# McPiFace-Pi4-V1_0.net
KiCad netlist of a schematic drawn in EAGLE
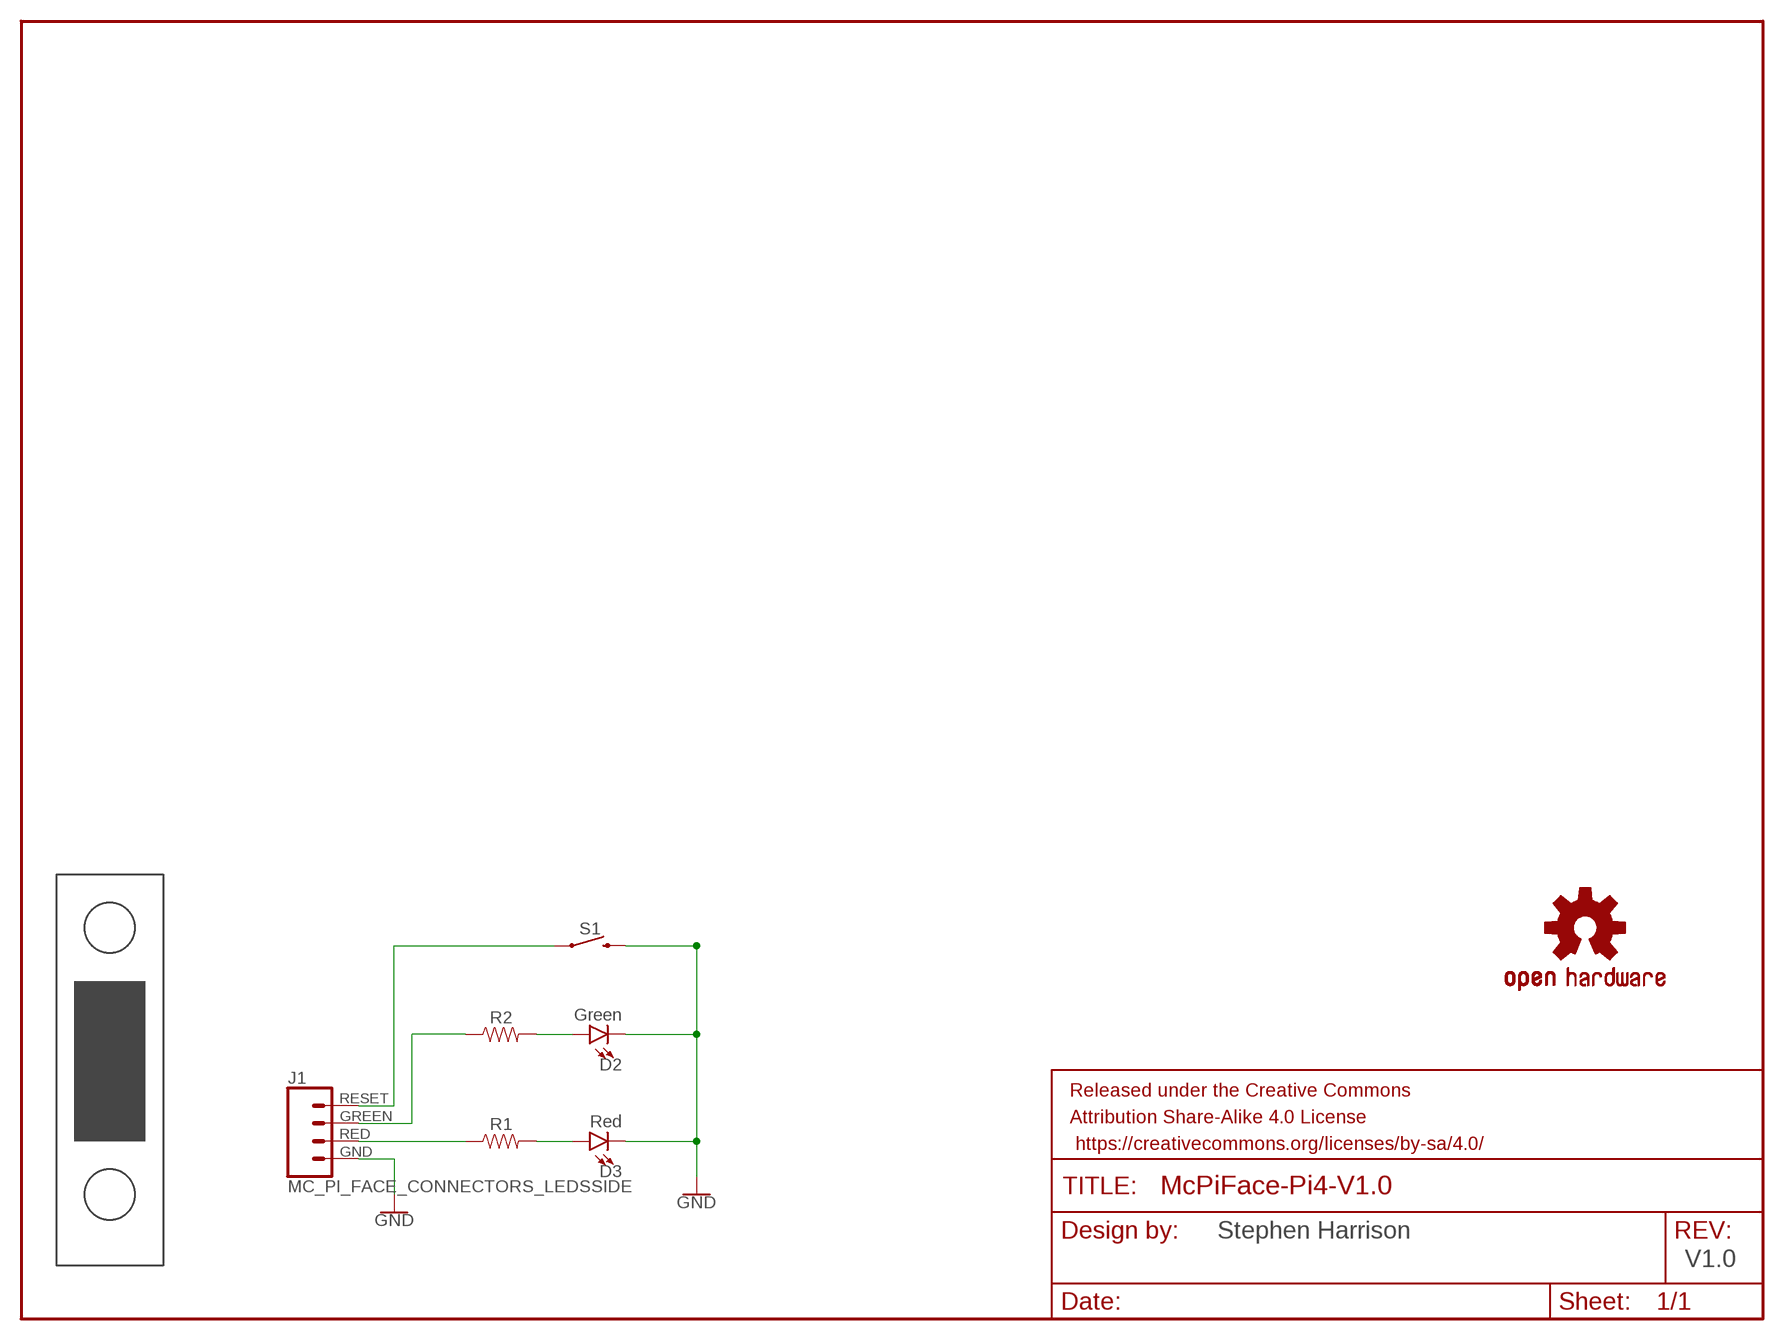
[diagram p0: schematic, sheet 1]

(export (version "E")
  (design (tool "Eeschema 10.0.6"))
  (components
    (comp (ref "D2")
      (value "Green")
      (footprint "eagle-import:LED-1206-BOTTOM-2.0MM")
      (libsource (lib "eagle-import") (part "LEDLED-1206-BOTTOM-2.0MM-GREEN"))
    )
    (comp (ref "D3")
      (value "Red")
      (footprint "eagle-import:LED-1206-BOTTOM-2.0MM")
      (libsource (lib "eagle-import") (part "LEDLED-1206-BOTTOM-2.0MM-RED"))
    )
    (comp (ref "FRAME1")
      (value "FRAME-LETTER")
      (footprint "eagle-import:CREATIVE_COMMONS")
      (libsource (lib "eagle-import") (part "FRAME-LETTER"))
    )
    (comp (ref "J1")
      (value "MC_PI_FACE_CONNECTORS_LEDSSIDE")
      (footprint "eagle-import:JST-4-SH-1.0MM-SIDE")
      (fields (field (name "MFG") "SM04B-SRSS-TB(LF)(SN)"))
      (libsource (lib "eagle-import") (part "MC_PI_FACE_CONNECTORS_LEDSSIDE"))
    )
    (comp (ref "LOGO1")
      (value "OSHW-LOGOL")
      (footprint "eagle-import:OSHW-LOGO-L")
      (libsource (lib "eagle-import") (part "OSHW-LOGOL"))
    )
    (comp (ref "R1")
      (value "RESISTOR0805")
      (footprint "eagle-import:0805")
      (libsource (lib "eagle-import") (part "RESISTOR0805"))
    )
    (comp (ref "R2")
      (value "RESISTOR0805")
      (footprint "eagle-import:0805")
      (libsource (lib "eagle-import") (part "RESISTOR0805"))
    )
    (comp (ref "S1")
      (value "MOMENTARY-SWITCH-SPSTTACKTILE_SWITCH_PTH_6.0MM_NO_TOP_RESIST")
      (footprint "eagle-import:TACTILE_SWITCH_PTH_6.0MM_NO_TOP_RESIST")
      (libsource (lib "eagle-import") (part "MOMENTARY-SWITCH-SPSTTACKTILE_SWITCH_PTH_6.0MM_NO_TOP_RESIST"))
    )
    (comp (ref "U$1")
      (value "MC_PI_4_FACE_PANEL")
      (footprint "eagle-import:MC_PI_4_FACE")
      (libsource (lib "eagle-import") (part "MC_PI_4_FACE_PANEL"))
    )
  )
  (nets
    (net (code "1") (name "GND") (class "Default")
      (node (ref "D2") (pin "C") (pinfunction "C_C") (pintype "passive"))
      (node (ref "D3") (pin "C") (pinfunction "C_C") (pintype "passive"))
      (node (ref "J1") (pin "GND") (pinfunction "GND_GND") (pintype "power_in"))
      (node (ref "S1") (pin "3") (pinfunction "2_3") (pintype "passive"))
    )
    (net (code "2") (name "Net-(D2-PadA)") (class "Default")
      (node (ref "D2") (pin "A") (pinfunction "A_A") (pintype "passive"))
      (node (ref "R2") (pin "2") (pinfunction "2_2") (pintype "passive"))
    )
    (net (code "3") (name "Net-(D3-PadA)") (class "Default")
      (node (ref "D3") (pin "A") (pinfunction "A_A") (pintype "passive"))
      (node (ref "R1") (pin "2") (pinfunction "2_2") (pintype "passive"))
    )
    (net (code "4") (name "Net-(J1-PadGREEN)") (class "Default")
      (node (ref "J1") (pin "GREEN") (pinfunction "GREEN_GREEN") (pintype "passive"))
      (node (ref "R2") (pin "1") (pinfunction "1_1") (pintype "passive"))
    )
    (net (code "5") (name "Net-(J1-PadRED)") (class "Default")
      (node (ref "J1") (pin "RED") (pinfunction "RED_RED") (pintype "passive"))
      (node (ref "R1") (pin "1") (pinfunction "1_1") (pintype "passive"))
    )
    (net (code "6") (name "Net-(J1-PadRESET)") (class "Default")
      (node (ref "J1") (pin "RESET") (pinfunction "RESET_RESET") (pintype "passive"))
      (node (ref "S1") (pin "1") (pinfunction "1_1") (pintype "passive"))
    )
  )
)
